# Simon-2022.net
KiCad netlist of a schematic drawn in EAGLE
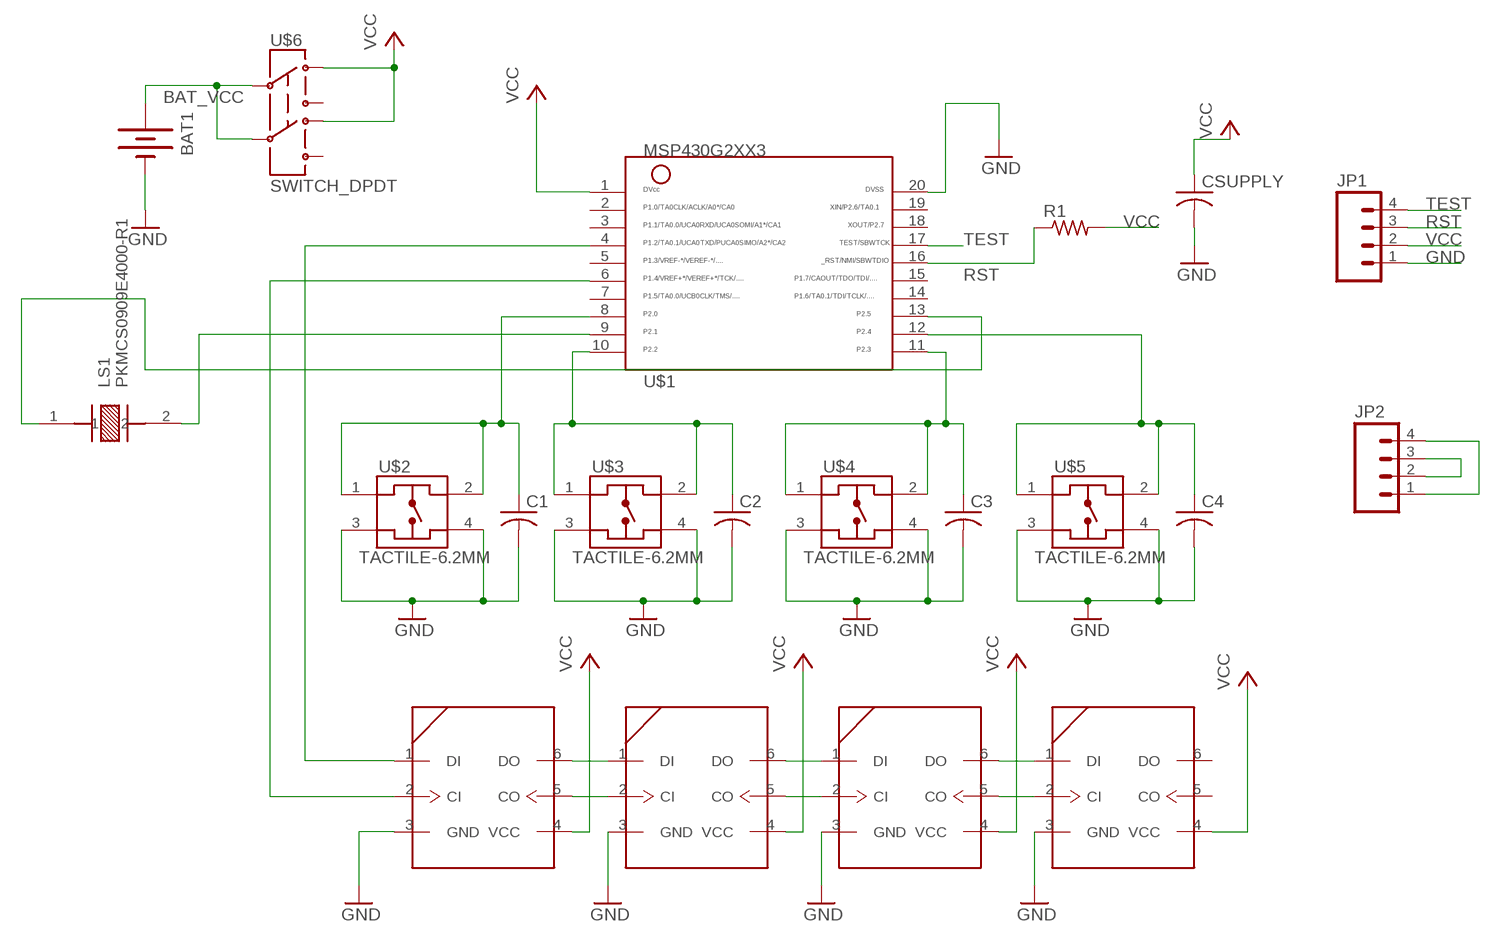
[diagram p0: schematic, sheet 1]

(export (version "E")
  (design (tool "Eeschema 10.0.6"))
  (components
    (comp (ref "BAT1")
      (value "BATTERY")
      (footprint "eagle-import:BATTERY_PACK_2AA")
      (libsource (lib "eagle-import") (part "BATTERY"))
    )
    (comp (ref "C1")
      (value "C-USC1206")
      (footprint "eagle-import:C1206")
      (libsource (lib "eagle-import") (part "C-USC1206"))
    )
    (comp (ref "C2")
      (value "C-USC1206")
      (footprint "eagle-import:C1206")
      (libsource (lib "eagle-import") (part "C-USC1206"))
    )
    (comp (ref "C3")
      (value "C-USC1206")
      (footprint "eagle-import:C1206")
      (libsource (lib "eagle-import") (part "C-USC1206"))
    )
    (comp (ref "C4")
      (value "C-USC1206")
      (footprint "eagle-import:C1206")
      (libsource (lib "eagle-import") (part "C-USC1206"))
    )
    (comp (ref "CSUPPLY")
      (value "C-USC1206")
      (footprint "eagle-import:C1206")
      (libsource (lib "eagle-import") (part "C-USC1206"))
    )
    (comp (ref "JP1")
      (value "M04LOCK")
      (footprint "eagle-import:1X04_LOCK")
      (libsource (lib "eagle-import") (part "M04LOCK"))
    )
    (comp (ref "JP2")
      (value "M04LOCK")
      (footprint "eagle-import:1X04_LOCK")
      (libsource (lib "eagle-import") (part "M04LOCK"))
    )
    (comp (ref "LED1")
      (value "APA102")
      (footprint "eagle-import:5050")
      (libsource (lib "eagle-import") (part "APA102"))
    )
    (comp (ref "LED2")
      (value "APA102")
      (footprint "eagle-import:5050")
      (libsource (lib "eagle-import") (part "APA102"))
    )
    (comp (ref "LED3")
      (value "APA102")
      (footprint "eagle-import:5050")
      (libsource (lib "eagle-import") (part "APA102"))
    )
    (comp (ref "LED4")
      (value "APA102")
      (footprint "eagle-import:5050")
      (libsource (lib "eagle-import") (part "APA102"))
    )
    (comp (ref "LS1")
      (value "PKMCS0909E4000-R1")
      (footprint "eagle-import:XDCR_PKMCS0909E4000-R1")
      (fields (field (name "DIGI-KEY_PART_NUMBER") "490-9647-1-ND") (field (name "MF") "Murata"))
      (libsource (lib "eagle-import") (part "PKMCS0909E4000-R1"))
    )
    (comp (ref "R1")
      (value "R-US_R1206")
      (footprint "eagle-import:R1206")
      (libsource (lib "eagle-import") (part "R-US_R1206"))
    )
    (comp (ref "U$1")
      (value "MSP430G2XX3TSSOP")
      (footprint "eagle-import:PW20")
      (libsource (lib "eagle-import") (part "MSP430G2XX3TSSOP"))
    )
    (comp (ref "U$2")
      (value "TACTILE-6.2MM")
      (footprint "eagle-import:222_AM")
      (libsource (lib "eagle-import") (part "TACTILE-6.2MM"))
    )
    (comp (ref "U$3")
      (value "TACTILE-6.2MM")
      (footprint "eagle-import:222_AM")
      (libsource (lib "eagle-import") (part "TACTILE-6.2MM"))
    )
    (comp (ref "U$4")
      (value "TACTILE-6.2MM")
      (footprint "eagle-import:222_AM")
      (libsource (lib "eagle-import") (part "TACTILE-6.2MM"))
    )
    (comp (ref "U$5")
      (value "TACTILE-6.2MM")
      (footprint "eagle-import:222_AM")
      (libsource (lib "eagle-import") (part "TACTILE-6.2MM"))
    )
    (comp (ref "U$6")
      (value "SWITCH_DPDT")
      (footprint "eagle-import:JS_DPDT_TH")
      (libsource (lib "eagle-import") (part "SWITCH_DPDT"))
    )
  )
  (nets
    (net (code "1") (name "/BAT_VCC") (class "Default")
      (node (ref "BAT1") (pin "3V") (pinfunction "+_3V") (pintype "power_in"))
      (node (ref "U$6") (pin "2") (pinfunction "2_2") (pintype "bidirectional"))
      (node (ref "U$6") (pin "5") (pinfunction "5_5") (pintype "bidirectional"))
    )
    (net (code "2") (name "/RST") (class "Default")
      (node (ref "JP1") (pin "3") (pinfunction "3_3") (pintype "passive"))
      (node (ref "R1") (pin "1") (pinfunction "1_1") (pintype "passive"))
      (node (ref "U$1") (pin "16") (pinfunction "16_16") (pintype "bidirectional"))
    )
    (net (code "3") (name "/TEST") (class "Default")
      (node (ref "JP1") (pin "4") (pinfunction "4_4") (pintype "passive"))
      (node (ref "U$1") (pin "17") (pinfunction "17_17") (pintype "bidirectional"))
    )
    (net (code "4") (name "GND") (class "Default")
      (node (ref "BAT1") (pin "GND") (pinfunction "-_GND") (pintype "power_in"))
      (node (ref "C1") (pin "2") (pinfunction "2_2") (pintype "passive"))
      (node (ref "C2") (pin "2") (pinfunction "2_2") (pintype "passive"))
      (node (ref "C3") (pin "2") (pinfunction "2_2") (pintype "passive"))
      (node (ref "C4") (pin "2") (pinfunction "2_2") (pintype "passive"))
      (node (ref "CSUPPLY") (pin "2") (pinfunction "2_2") (pintype "passive"))
      (node (ref "JP1") (pin "1") (pinfunction "1_1") (pintype "passive"))
      (node (ref "LED1") (pin "3") (pinfunction "GND_3") (pintype "power_in"))
      (node (ref "LED2") (pin "3") (pinfunction "GND_3") (pintype "power_in"))
      (node (ref "LED3") (pin "3") (pinfunction "GND_3") (pintype "power_in"))
      (node (ref "LED4") (pin "3") (pinfunction "GND_3") (pintype "power_in"))
      (node (ref "U$1") (pin "20") (pinfunction "20_20") (pintype "bidirectional"))
      (node (ref "U$2") (pin "3") (pinfunction "2_3") (pintype "passive"))
      (node (ref "U$2") (pin "4") (pinfunction "4_4") (pintype "passive"))
      (node (ref "U$3") (pin "3") (pinfunction "2_3") (pintype "passive"))
      (node (ref "U$3") (pin "4") (pinfunction "4_4") (pintype "passive"))
      (node (ref "U$4") (pin "3") (pinfunction "2_3") (pintype "passive"))
      (node (ref "U$4") (pin "4") (pinfunction "4_4") (pintype "passive"))
      (node (ref "U$5") (pin "3") (pinfunction "2_3") (pintype "passive"))
      (node (ref "U$5") (pin "4") (pinfunction "4_4") (pintype "passive"))
    )
    (net (code "5") (name "Net-(JP2-Pad1)") (class "Default")
      (node (ref "JP2") (pin "1") (pinfunction "1_1") (pintype "passive"))
      (node (ref "JP2") (pin "4") (pinfunction "4_4") (pintype "passive"))
    )
    (net (code "6") (name "Net-(JP2-Pad2)") (class "Default")
      (node (ref "JP2") (pin "2") (pinfunction "2_2") (pintype "passive"))
      (node (ref "JP2") (pin "3") (pinfunction "3_3") (pintype "passive"))
    )
    (net (code "7") (name "Net-(LED1-CI)") (class "Default")
      (node (ref "LED1") (pin "2") (pinfunction "CI_2") (pintype "input"))
      (node (ref "U$1") (pin "6") (pinfunction "6_6") (pintype "bidirectional"))
    )
    (net (code "8") (name "Net-(LED1-CO)") (class "Default")
      (node (ref "LED1") (pin "5") (pinfunction "CO_5") (pintype "output"))
      (node (ref "LED2") (pin "2") (pinfunction "CI_2") (pintype "input"))
    )
    (net (code "9") (name "Net-(LED1-DI)") (class "Default")
      (node (ref "LED1") (pin "1") (pinfunction "DI_1") (pintype "input"))
      (node (ref "U$1") (pin "4") (pinfunction "4_4") (pintype "bidirectional"))
    )
    (net (code "10") (name "Net-(LED1-DO)") (class "Default")
      (node (ref "LED1") (pin "6") (pinfunction "DO_6") (pintype "output"))
      (node (ref "LED2") (pin "1") (pinfunction "DI_1") (pintype "input"))
    )
    (net (code "11") (name "Net-(LED2-CO)") (class "Default")
      (node (ref "LED2") (pin "5") (pinfunction "CO_5") (pintype "output"))
      (node (ref "LED3") (pin "2") (pinfunction "CI_2") (pintype "input"))
    )
    (net (code "12") (name "Net-(LED2-DO)") (class "Default")
      (node (ref "LED2") (pin "6") (pinfunction "DO_6") (pintype "output"))
      (node (ref "LED3") (pin "1") (pinfunction "DI_1") (pintype "input"))
    )
    (net (code "13") (name "Net-(LED3-CO)") (class "Default")
      (node (ref "LED3") (pin "5") (pinfunction "CO_5") (pintype "output"))
      (node (ref "LED4") (pin "2") (pinfunction "CI_2") (pintype "input"))
    )
    (net (code "14") (name "Net-(LED3-DO)") (class "Default")
      (node (ref "LED3") (pin "6") (pinfunction "DO_6") (pintype "output"))
      (node (ref "LED4") (pin "1") (pinfunction "DI_1") (pintype "input"))
    )
    (net (code "15") (name "Net-(LS1-Pad1)") (class "Default")
      (node (ref "LS1") (pin "1") (pinfunction "1_1") (pintype "passive"))
      (node (ref "U$1") (pin "13") (pinfunction "13_13") (pintype "bidirectional"))
    )
    (net (code "16") (name "Net-(LS1-Pad2)") (class "Default")
      (node (ref "LS1") (pin "2") (pinfunction "2_2") (pintype "passive"))
      (node (ref "U$1") (pin "9") (pinfunction "9_9") (pintype "bidirectional"))
    )
    (net (code "17") (name "Net-(U$2-3)") (class "Default")
      (node (ref "C1") (pin "1") (pinfunction "1_1") (pintype "passive"))
      (node (ref "U$1") (pin "8") (pinfunction "8_8") (pintype "bidirectional"))
      (node (ref "U$2") (pin "1") (pinfunction "1_1") (pintype "passive"))
      (node (ref "U$2") (pin "2") (pinfunction "3_2") (pintype "passive"))
    )
    (net (code "18") (name "Net-(U$3-3)") (class "Default")
      (node (ref "C2") (pin "1") (pinfunction "1_1") (pintype "passive"))
      (node (ref "U$1") (pin "10") (pinfunction "10_10") (pintype "bidirectional"))
      (node (ref "U$3") (pin "1") (pinfunction "1_1") (pintype "passive"))
      (node (ref "U$3") (pin "2") (pinfunction "3_2") (pintype "passive"))
    )
    (net (code "19") (name "Net-(U$4-3)") (class "Default")
      (node (ref "C3") (pin "1") (pinfunction "1_1") (pintype "passive"))
      (node (ref "U$1") (pin "11") (pinfunction "11_11") (pintype "bidirectional"))
      (node (ref "U$4") (pin "1") (pinfunction "1_1") (pintype "passive"))
      (node (ref "U$4") (pin "2") (pinfunction "3_2") (pintype "passive"))
    )
    (net (code "20") (name "Net-(U$5-3)") (class "Default")
      (node (ref "C4") (pin "1") (pinfunction "1_1") (pintype "passive"))
      (node (ref "U$1") (pin "12") (pinfunction "12_12") (pintype "bidirectional"))
      (node (ref "U$5") (pin "1") (pinfunction "1_1") (pintype "passive"))
      (node (ref "U$5") (pin "2") (pinfunction "3_2") (pintype "passive"))
    )
    (net (code "21") (name "VCC") (class "Default")
      (node (ref "CSUPPLY") (pin "1") (pinfunction "1_1") (pintype "passive"))
      (node (ref "JP1") (pin "2") (pinfunction "2_2") (pintype "passive"))
      (node (ref "LED1") (pin "4") (pinfunction "VCC_4") (pintype "power_in"))
      (node (ref "LED2") (pin "4") (pinfunction "VCC_4") (pintype "power_in"))
      (node (ref "LED3") (pin "4") (pinfunction "VCC_4") (pintype "power_in"))
      (node (ref "LED4") (pin "4") (pinfunction "VCC_4") (pintype "power_in"))
      (node (ref "R1") (pin "2") (pinfunction "2_2") (pintype "passive"))
      (node (ref "U$1") (pin "1") (pinfunction "1_1") (pintype "bidirectional"))
      (node (ref "U$6") (pin "1") (pinfunction "1_1") (pintype "bidirectional"))
      (node (ref "U$6") (pin "4") (pinfunction "4_4") (pintype "bidirectional"))
    )
    (net (code "22") (name "unconnected-(LED4-CO-Pad5)") (class "Default")
      (node (ref "LED4") (pin "5") (pinfunction "CO_5") (pintype "output"))
    )
    (net (code "23") (name "unconnected-(LED4-DO-Pad6)") (class "Default")
      (node (ref "LED4") (pin "6") (pinfunction "DO_6") (pintype "output"))
    )
    (net (code "24") (name "unconnected-(U$1-Pad2)") (class "Default")
      (node (ref "U$1") (pin "2") (pinfunction "2_2") (pintype "bidirectional"))
    )
    (net (code "25") (name "unconnected-(U$1-Pad3)") (class "Default")
      (node (ref "U$1") (pin "3") (pinfunction "3_3") (pintype "bidirectional"))
    )
    (net (code "26") (name "unconnected-(U$1-Pad5)") (class "Default")
      (node (ref "U$1") (pin "5") (pinfunction "5_5") (pintype "bidirectional"))
    )
    (net (code "27") (name "unconnected-(U$1-Pad7)") (class "Default")
      (node (ref "U$1") (pin "7") (pinfunction "7_7") (pintype "bidirectional"))
    )
    (net (code "28") (name "unconnected-(U$1-Pad14)") (class "Default")
      (node (ref "U$1") (pin "14") (pinfunction "14_14") (pintype "bidirectional"))
    )
    (net (code "29") (name "unconnected-(U$1-Pad15)") (class "Default")
      (node (ref "U$1") (pin "15") (pinfunction "15_15") (pintype "bidirectional"))
    )
    (net (code "30") (name "unconnected-(U$1-Pad18)") (class "Default")
      (node (ref "U$1") (pin "18") (pinfunction "18_18") (pintype "bidirectional"))
    )
    (net (code "31") (name "unconnected-(U$1-Pad19)") (class "Default")
      (node (ref "U$1") (pin "19") (pinfunction "19_19") (pintype "bidirectional"))
    )
    (net (code "32") (name "unconnected-(U$6-Pad3)") (class "Default")
      (node (ref "U$6") (pin "3") (pinfunction "3_3") (pintype "bidirectional"))
    )
    (net (code "33") (name "unconnected-(U$6-Pad6)") (class "Default")
      (node (ref "U$6") (pin "6") (pinfunction "6_6") (pintype "bidirectional"))
    )
  )
)
